# MIDIWidgetRevB.net
KiCad netlist of a schematic drawn in EAGLE
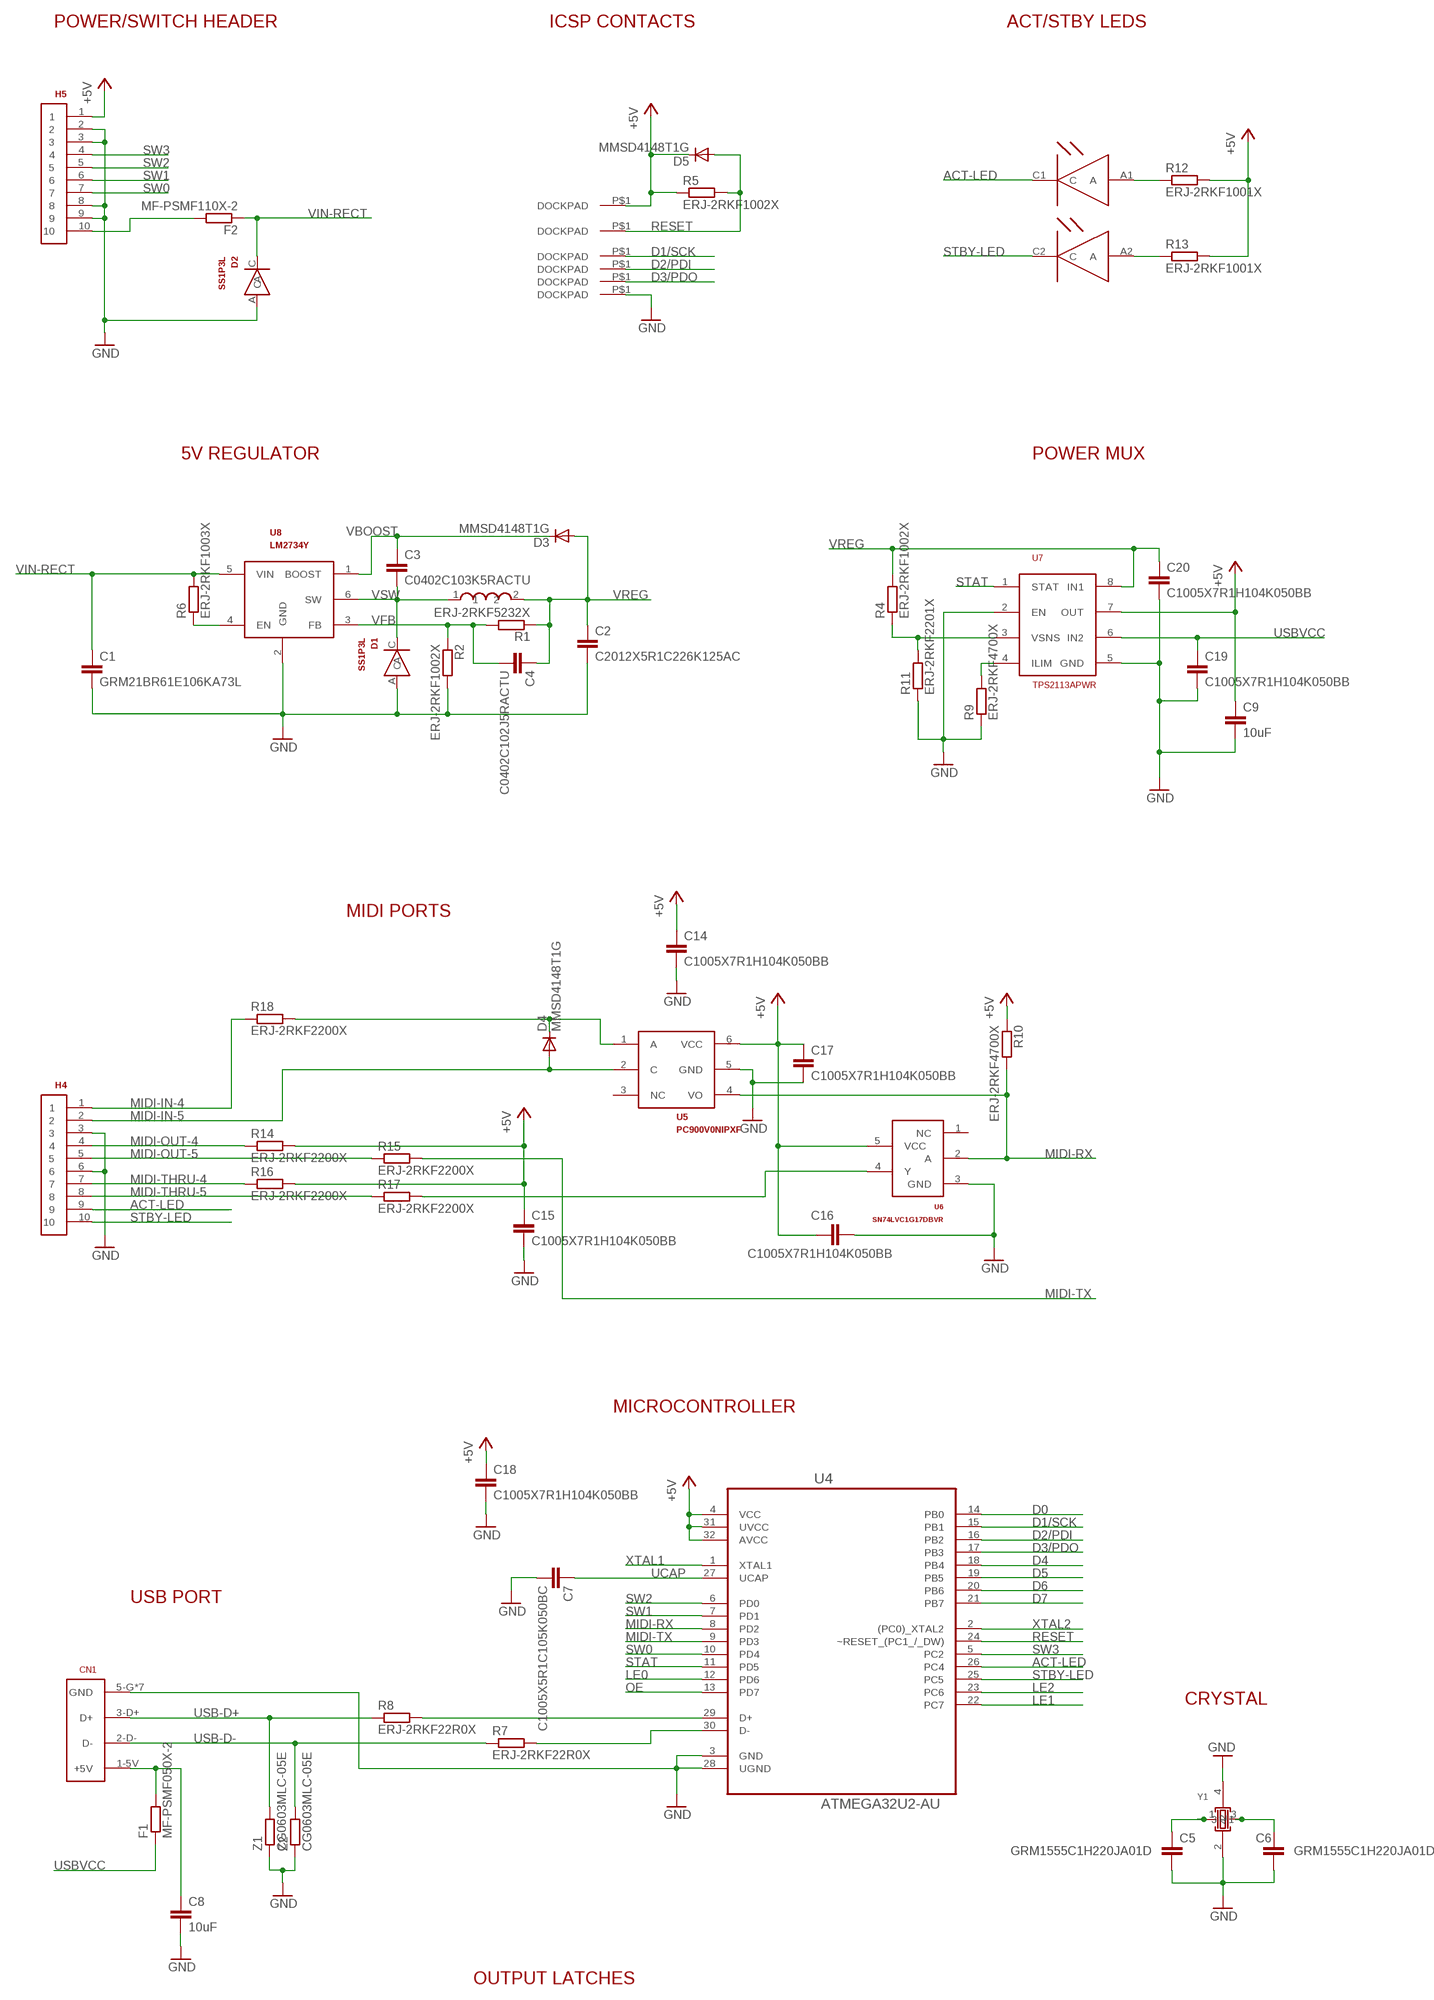
[diagram p0: schematic, sheet 1, part 1 of 2]
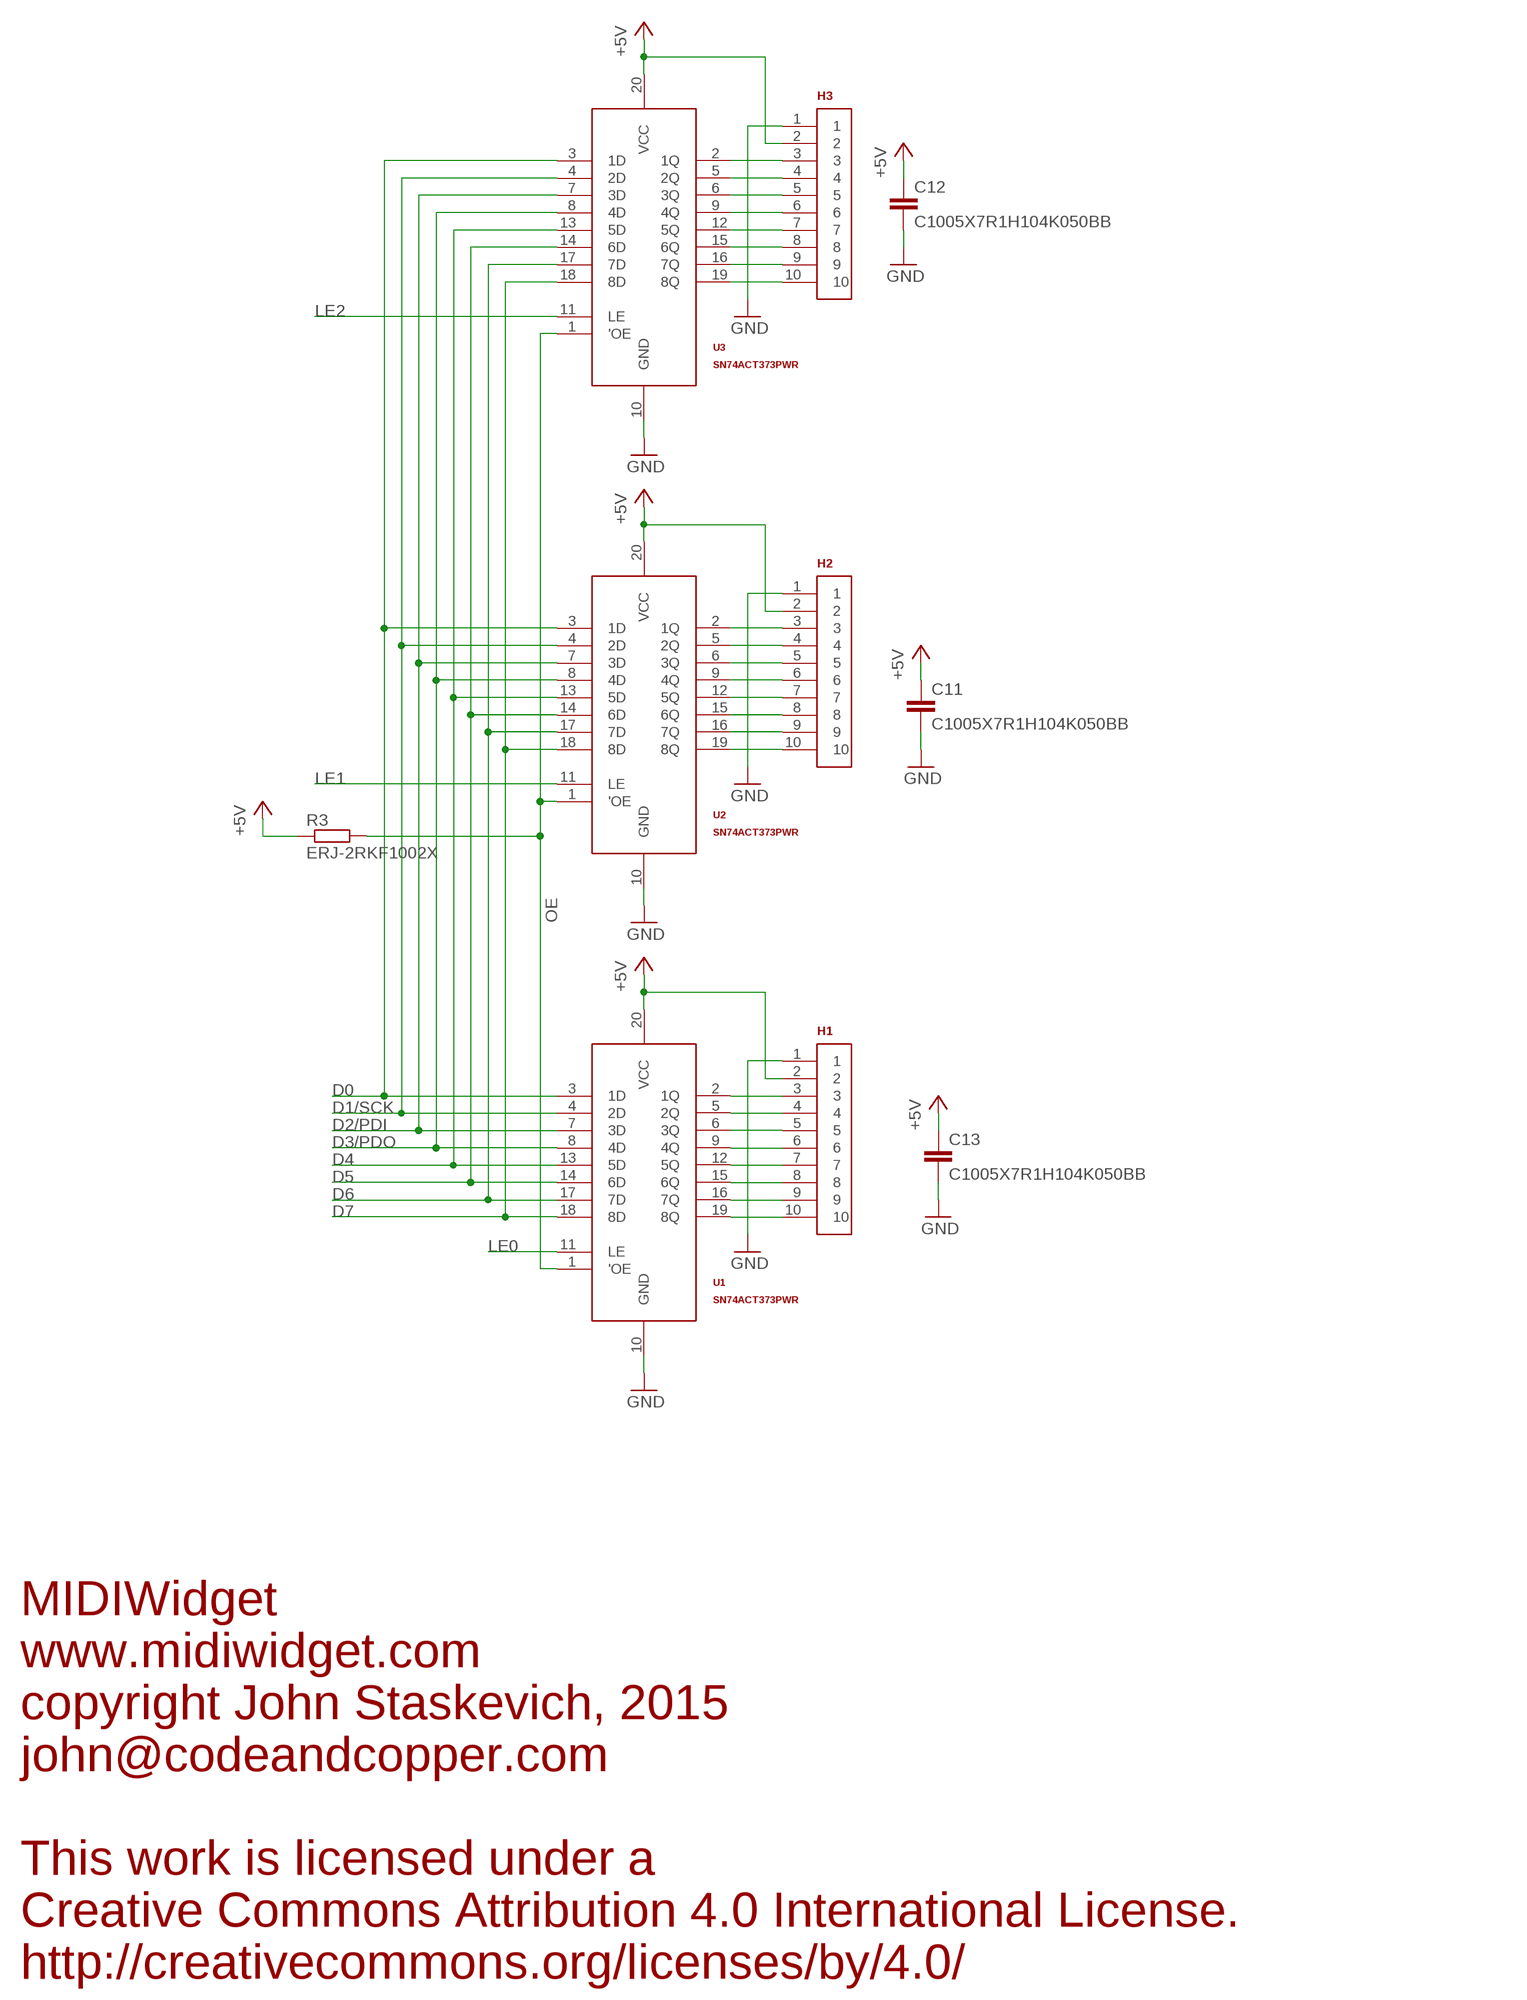
[diagram p1: schematic, sheet 1, part 2 of 2]

(export (version "E")
  (design (tool "Eeschema 10.0.6"))
  (components
    (comp (ref "C1")
      (value "GRM21BR61E106KA73L")
      (footprint "eagle-import:C0805")
      (libsource (lib "eagle-import") (part "C-EUC0805"))
    )
    (comp (ref "C2")
      (value "C2012X5R1C226K125AC")
      (footprint "eagle-import:C0805")
      (libsource (lib "eagle-import") (part "C-EUC0805"))
    )
    (comp (ref "C3")
      (value "C0402C103K5RACTU")
      (footprint "eagle-import:C0402")
      (libsource (lib "eagle-import") (part "C-EUC0402"))
    )
    (comp (ref "C4")
      (value "C0402C102J5RACTU")
      (footprint "eagle-import:C0402")
      (libsource (lib "eagle-import") (part "C-EUC0402"))
    )
    (comp (ref "C5")
      (value "GRM1555C1H220JA01D")
      (footprint "eagle-import:C0402")
      (libsource (lib "eagle-import") (part "C-EUC0402"))
    )
    (comp (ref "C6")
      (value "GRM1555C1H220JA01D")
      (footprint "eagle-import:C0402")
      (libsource (lib "eagle-import") (part "C-EUC0402"))
    )
    (comp (ref "C7")
      (value "C1005X5R1C105K050BC")
      (footprint "eagle-import:C0402")
      (libsource (lib "eagle-import") (part "C-EUC0402"))
    )
    (comp (ref "C8")
      (value "10uF")
      (footprint "eagle-import:C0805")
      (libsource (lib "eagle-import") (part "C-EUC0805"))
    )
    (comp (ref "C9")
      (value "10uF")
      (footprint "eagle-import:C0805")
      (libsource (lib "eagle-import") (part "C-EUC0805"))
    )
    (comp (ref "C11")
      (value "C1005X7R1H104K050BB")
      (footprint "eagle-import:C0402")
      (libsource (lib "eagle-import") (part "C-EUC0402"))
    )
    (comp (ref "C12")
      (value "C1005X7R1H104K050BB")
      (footprint "eagle-import:C0402")
      (libsource (lib "eagle-import") (part "C-EUC0402"))
    )
    (comp (ref "C13")
      (value "C1005X7R1H104K050BB")
      (footprint "eagle-import:C0402")
      (libsource (lib "eagle-import") (part "C-EUC0402"))
    )
    (comp (ref "C14")
      (value "C1005X7R1H104K050BB")
      (footprint "eagle-import:C0402")
      (libsource (lib "eagle-import") (part "C-EUC0402"))
    )
    (comp (ref "C15")
      (value "C1005X7R1H104K050BB")
      (footprint "eagle-import:C0402")
      (libsource (lib "eagle-import") (part "C-EUC0402"))
    )
    (comp (ref "C16")
      (value "C1005X7R1H104K050BB")
      (footprint "eagle-import:C0402")
      (libsource (lib "eagle-import") (part "C-EUC0402"))
    )
    (comp (ref "C17")
      (value "C1005X7R1H104K050BB")
      (footprint "eagle-import:C0402")
      (libsource (lib "eagle-import") (part "C-EUC0402"))
    )
    (comp (ref "C18")
      (value "C1005X7R1H104K050BB")
      (footprint "eagle-import:C0402")
      (libsource (lib "eagle-import") (part "C-EUC0402"))
    )
    (comp (ref "C19")
      (value "C1005X7R1H104K050BB")
      (footprint "eagle-import:C0402")
      (libsource (lib "eagle-import") (part "C-EUC0402"))
    )
    (comp (ref "C20")
      (value "C1005X7R1H104K050BB")
      (footprint "eagle-import:C0402")
      (libsource (lib "eagle-import") (part "C-EUC0402"))
    )
    (comp (ref "CN1")
      (value "10118192-0001LF")
      (footprint "eagle-import:USB-MICRO-B")
      (libsource (lib "eagle-import") (part "USB-B"))
    )
    (comp (ref "D1")
      (value "SS1P3L")
      (footprint "eagle-import:DO-220AA(SMP)")
      (libsource (lib "eagle-import") (part "DIODE"))
    )
    (comp (ref "D2")
      (value "SS1P3L")
      (footprint "eagle-import:DO-220AA(SMP)")
      (libsource (lib "eagle-import") (part "DIODE"))
    )
    (comp (ref "D3")
      (value "MMSD4148T1G")
      (footprint "eagle-import:SOD123")
      (libsource (lib "eagle-import") (part "1N4148SOD123"))
    )
    (comp (ref "D4")
      (value "MMSD4148T1G")
      (footprint "eagle-import:SOD123")
      (libsource (lib "eagle-import") (part "1N4148SOD123"))
    )
    (comp (ref "D5")
      (value "MMSD4148T1G")
      (footprint "eagle-import:SOD123")
      (libsource (lib "eagle-import") (part "1N4148SOD123"))
    )
    (comp (ref "DOCK-GND")
      (value "DOCKPAD")
      (footprint "eagle-import:DOCKPAD-ROUND-2.0MM")
      (libsource (lib "eagle-import") (part "DOCKPAD"))
    )
    (comp (ref "DOCK-PDI")
      (value "DOCKPAD")
      (footprint "eagle-import:DOCKPAD-ROUND-2.0MM")
      (libsource (lib "eagle-import") (part "DOCKPAD"))
    )
    (comp (ref "DOCK-PDO")
      (value "DOCKPAD")
      (footprint "eagle-import:DOCKPAD-ROUND-2.0MM")
      (libsource (lib "eagle-import") (part "DOCKPAD"))
    )
    (comp (ref "DOCK-RESET")
      (value "DOCKPAD")
      (footprint "eagle-import:DOCKPAD-ROUND-2.0MM")
      (libsource (lib "eagle-import") (part "DOCKPAD"))
    )
    (comp (ref "DOCK-SCK")
      (value "DOCKPAD")
      (footprint "eagle-import:DOCKPAD-ROUND-2.0MM")
      (libsource (lib "eagle-import") (part "DOCKPAD"))
    )
    (comp (ref "DOCK-VCC")
      (value "DOCKPAD")
      (footprint "eagle-import:DOCKPAD-ROUND-2.0MM")
      (libsource (lib "eagle-import") (part "DOCKPAD"))
    )
    (comp (ref "F1")
      (value "MF-PSMF050X-2")
      (footprint "eagle-import:R0805")
      (libsource (lib "eagle-import") (part "R-EU_R0805"))
    )
    (comp (ref "F2")
      (value "MF-PSMF110X-2")
      (footprint "eagle-import:R0805")
      (libsource (lib "eagle-import") (part "R-EU_R0805"))
    )
    (comp (ref "H1")
      (value "TERMINAL-BLOCK-10POS")
      (footprint "eagle-import:TB-2-54-10POS")
      (libsource (lib "eagle-import") (part "TERMINAL-BLOCK-10POS"))
    )
    (comp (ref "H2")
      (value "TERMINAL-BLOCK-10POS")
      (footprint "eagle-import:TB-2-54-10POS")
      (libsource (lib "eagle-import") (part "TERMINAL-BLOCK-10POS"))
    )
    (comp (ref "H3")
      (value "TERMINAL-BLOCK-10POS")
      (footprint "eagle-import:TB-2-54-10POS")
      (libsource (lib "eagle-import") (part "TERMINAL-BLOCK-10POS"))
    )
    (comp (ref "H4")
      (value "TERMINAL-BLOCK-10POS")
      (footprint "eagle-import:TB-2-54-10POS")
      (libsource (lib "eagle-import") (part "TERMINAL-BLOCK-10POS"))
    )
    (comp (ref "H5")
      (value "TERMINAL-BLOCK-10POS")
      (footprint "eagle-import:TB-2-54-10POS")
      (libsource (lib "eagle-import") (part "TERMINAL-BLOCK-10POS"))
    )
    (comp (ref "L1")
      (value "SLF7055T-220M1R7-3PF")
      (footprint "eagle-import:SLF7055")
      (libsource (lib "eagle-import") (part "INDUCTOR-SMT"))
    )
    (comp (ref "LED")
      (value "HSMF-C155")
      (footprint "eagle-import:LUMEX-1210-DUAL-LED")
      (libsource (lib "eagle-import") (part "DUAL-LED"))
    )
    (comp (ref "R1")
      (value "ERJ-2RKF5232X")
      (footprint "eagle-import:R0402")
      (libsource (lib "eagle-import") (part "R-EU_R0402"))
    )
    (comp (ref "R2")
      (value "ERJ-2RKF1002X")
      (footprint "eagle-import:R0402")
      (libsource (lib "eagle-import") (part "R-EU_R0402"))
    )
    (comp (ref "R3")
      (value "ERJ-2RKF1002X")
      (footprint "eagle-import:R0402")
      (libsource (lib "eagle-import") (part "R-EU_R0402"))
    )
    (comp (ref "R4")
      (value "ERJ-2RKF1002X")
      (footprint "eagle-import:R0402")
      (libsource (lib "eagle-import") (part "R-EU_R0402"))
    )
    (comp (ref "R5")
      (value "ERJ-2RKF1002X")
      (footprint "eagle-import:R0402")
      (libsource (lib "eagle-import") (part "R-EU_R0402"))
    )
    (comp (ref "R6")
      (value "ERJ-2RKF1003X")
      (footprint "eagle-import:R0402")
      (libsource (lib "eagle-import") (part "R-EU_R0402"))
    )
    (comp (ref "R7")
      (value "ERJ-2RKF22R0X")
      (footprint "eagle-import:R0402")
      (libsource (lib "eagle-import") (part "R-EU_R0402"))
    )
    (comp (ref "R8")
      (value "ERJ-2RKF22R0X")
      (footprint "eagle-import:R0402")
      (libsource (lib "eagle-import") (part "R-EU_R0402"))
    )
    (comp (ref "R9")
      (value "ERJ-2RKF4700X")
      (footprint "eagle-import:R0402")
      (libsource (lib "eagle-import") (part "R-EU_R0402"))
    )
    (comp (ref "R10")
      (value "ERJ-2RKF4700X")
      (footprint "eagle-import:R0402")
      (libsource (lib "eagle-import") (part "R-EU_R0402"))
    )
    (comp (ref "R11")
      (value "ERJ-2RKF2201X")
      (footprint "eagle-import:R0402")
      (libsource (lib "eagle-import") (part "R-EU_R0402"))
    )
    (comp (ref "R12")
      (value "ERJ-2RKF1001X")
      (footprint "eagle-import:R0402")
      (libsource (lib "eagle-import") (part "R-EU_R0402"))
    )
    (comp (ref "R13")
      (value "ERJ-2RKF1001X")
      (footprint "eagle-import:R0402")
      (libsource (lib "eagle-import") (part "R-EU_R0402"))
    )
    (comp (ref "R14")
      (value "ERJ-2RKF2200X")
      (footprint "eagle-import:R0402")
      (libsource (lib "eagle-import") (part "R-EU_R0402"))
    )
    (comp (ref "R15")
      (value "ERJ-2RKF2200X")
      (footprint "eagle-import:R0402")
      (libsource (lib "eagle-import") (part "R-EU_R0402"))
    )
    (comp (ref "R16")
      (value "ERJ-2RKF2200X")
      (footprint "eagle-import:R0402")
      (libsource (lib "eagle-import") (part "R-EU_R0402"))
    )
    (comp (ref "R17")
      (value "ERJ-2RKF2200X")
      (footprint "eagle-import:R0402")
      (libsource (lib "eagle-import") (part "R-EU_R0402"))
    )
    (comp (ref "R18")
      (value "ERJ-2RKF2200X")
      (footprint "eagle-import:R0402")
      (libsource (lib "eagle-import") (part "R-EU_R0402"))
    )
    (comp (ref "U1")
      (value "SN74ACT373PWR")
      (footprint "eagle-import:TSSOP-20")
      (libsource (lib "eagle-import") (part "74ABT373"))
    )
    (comp (ref "U2")
      (value "SN74ACT373PWR")
      (footprint "eagle-import:TSSOP-20")
      (libsource (lib "eagle-import") (part "74ABT373"))
    )
    (comp (ref "U3")
      (value "SN74ACT373PWR")
      (footprint "eagle-import:TSSOP-20")
      (libsource (lib "eagle-import") (part "74ABT373"))
    )
    (comp (ref "U4")
      (value "ATMEGA32U2-AU")
      (footprint "eagle-import:QFP80P900X900X120-32N")
      (libsource (lib "eagle-import") (part "ATMEGA32U2-AU"))
    )
    (comp (ref "U5")
      (value "PC900V0NIPXF")
      (footprint "eagle-import:SMT-6")
      (libsource (lib "eagle-import") (part "PC900V"))
    )
    (comp (ref "U6")
      (value "SN74LVC1G17DBVR")
      (footprint "eagle-import:SOT23-5-GOOD")
      (libsource (lib "eagle-import") (part "SN74LVC1G17"))
    )
    (comp (ref "U7")
      (value "TPS2113APWR")
      (footprint "eagle-import:TSSOP-8-NAKED")
      (libsource (lib "eagle-import") (part "TPS2112NAKED"))
    )
    (comp (ref "U8")
      (value "LM2734Y")
      (footprint "eagle-import:TSOT-6")
      (libsource (lib "eagle-import") (part "LM2734"))
    )
    (comp (ref "Y1")
      (value "403C35E16M00000")
      (footprint "eagle-import:CRYSTAL-32-25MM")
      (libsource (lib "eagle-import") (part "CTS-403-CRYSTAL"))
    )
    (comp (ref "Z1")
      (value "CG0603MLC-05E")
      (footprint "eagle-import:R0603")
      (libsource (lib "eagle-import") (part "R-EU_R0603"))
    )
    (comp (ref "Z2")
      (value "CG0603MLC-05E")
      (footprint "eagle-import:R0603")
      (libsource (lib "eagle-import") (part "R-EU_R0603"))
    )
  )
  (nets
    (net (code "1") (name "+5V") (class "Default")
      (node (ref "C11") (pin "1") (pinfunction "1_1") (pintype "passive"))
      (node (ref "C12") (pin "1") (pinfunction "1_1") (pintype "passive"))
      (node (ref "C13") (pin "1") (pinfunction "1_1") (pintype "passive"))
      (node (ref "C14") (pin "1") (pinfunction "1_1") (pintype "passive"))
      (node (ref "C15") (pin "1") (pinfunction "1_1") (pintype "passive"))
      (node (ref "C16") (pin "1") (pinfunction "1_1") (pintype "passive"))
      (node (ref "C17") (pin "1") (pinfunction "1_1") (pintype "passive"))
      (node (ref "C18") (pin "1") (pinfunction "1_1") (pintype "passive"))
      (node (ref "C9") (pin "1") (pinfunction "1_1") (pintype "passive"))
      (node (ref "D5") (pin "C") (pinfunction "C_C") (pintype "passive"))
      (node (ref "DOCK-VCC") (pin "P$1") (pinfunction "DOCKPAD_P$1") (pintype "bidirectional"))
      (node (ref "H1") (pin "2") (pinfunction "2_2") (pintype "bidirectional"))
      (node (ref "H2") (pin "2") (pinfunction "2_2") (pintype "bidirectional"))
      (node (ref "H3") (pin "2") (pinfunction "2_2") (pintype "bidirectional"))
      (node (ref "H5") (pin "1") (pinfunction "1_1") (pintype "bidirectional"))
      (node (ref "R10") (pin "1") (pinfunction "1_1") (pintype "passive"))
      (node (ref "R12") (pin "2") (pinfunction "2_2") (pintype "passive"))
      (node (ref "R13") (pin "2") (pinfunction "2_2") (pintype "passive"))
      (node (ref "R14") (pin "2") (pinfunction "2_2") (pintype "passive"))
      (node (ref "R16") (pin "2") (pinfunction "2_2") (pintype "passive"))
      (node (ref "R3") (pin "1") (pinfunction "1_1") (pintype "passive"))
      (node (ref "R5") (pin "1") (pinfunction "1_1") (pintype "passive"))
      (node (ref "U1") (pin "20") (pinfunction "VCC_20") (pintype "bidirectional"))
      (node (ref "U2") (pin "20") (pinfunction "VCC_20") (pintype "bidirectional"))
      (node (ref "U3") (pin "20") (pinfunction "VCC_20") (pintype "bidirectional"))
      (node (ref "U4") (pin "31") (pinfunction "UVCC_31") (pintype "power_in"))
      (node (ref "U4") (pin "32") (pinfunction "AVCC_32") (pintype "power_in"))
      (node (ref "U4") (pin "4") (pinfunction "VCC_4") (pintype "power_in"))
      (node (ref "U5") (pin "6") (pinfunction "VCC_6") (pintype "bidirectional"))
      (node (ref "U6") (pin "5") (pinfunction "VCC_5") (pintype "bidirectional"))
      (node (ref "U7") (pin "7") (pinfunction "OUT_7") (pintype "bidirectional"))
    )
    (net (code "2") (name "/ACT-LED") (class "Default")
      (node (ref "H4") (pin "9") (pinfunction "9_9") (pintype "bidirectional"))
      (node (ref "LED") (pin "C1") (pinfunction "C_C1") (pintype "bidirectional"))
      (node (ref "U4") (pin "26") (pinfunction "PC4_26") (pintype "bidirectional"))
    )
    (net (code "3") (name "/D0") (class "Default")
      (node (ref "U1") (pin "3") (pinfunction "1D_3") (pintype "bidirectional"))
      (node (ref "U2") (pin "3") (pinfunction "1D_3") (pintype "bidirectional"))
      (node (ref "U3") (pin "3") (pinfunction "1D_3") (pintype "bidirectional"))
      (node (ref "U4") (pin "14") (pinfunction "PB0_14") (pintype "bidirectional"))
    )
    (net (code "4") (name "/D1{slash}SCK") (class "Default")
      (node (ref "DOCK-SCK") (pin "P$1") (pinfunction "DOCKPAD_P$1") (pintype "bidirectional"))
      (node (ref "U1") (pin "4") (pinfunction "2D_4") (pintype "bidirectional"))
      (node (ref "U2") (pin "4") (pinfunction "2D_4") (pintype "bidirectional"))
      (node (ref "U3") (pin "4") (pinfunction "2D_4") (pintype "bidirectional"))
      (node (ref "U4") (pin "15") (pinfunction "PB1_15") (pintype "bidirectional"))
    )
    (net (code "5") (name "/D2{slash}PDI") (class "Default")
      (node (ref "DOCK-PDI") (pin "P$1") (pinfunction "DOCKPAD_P$1") (pintype "bidirectional"))
      (node (ref "U1") (pin "7") (pinfunction "3D_7") (pintype "bidirectional"))
      (node (ref "U2") (pin "7") (pinfunction "3D_7") (pintype "bidirectional"))
      (node (ref "U3") (pin "7") (pinfunction "3D_7") (pintype "bidirectional"))
      (node (ref "U4") (pin "16") (pinfunction "PB2_16") (pintype "bidirectional"))
    )
    (net (code "6") (name "/D3{slash}PDO") (class "Default")
      (node (ref "DOCK-PDO") (pin "P$1") (pinfunction "DOCKPAD_P$1") (pintype "bidirectional"))
      (node (ref "U1") (pin "8") (pinfunction "4D_8") (pintype "bidirectional"))
      (node (ref "U2") (pin "8") (pinfunction "4D_8") (pintype "bidirectional"))
      (node (ref "U3") (pin "8") (pinfunction "4D_8") (pintype "bidirectional"))
      (node (ref "U4") (pin "17") (pinfunction "PB3_17") (pintype "bidirectional"))
    )
    (net (code "7") (name "/D4") (class "Default")
      (node (ref "U1") (pin "13") (pinfunction "5D_13") (pintype "bidirectional"))
      (node (ref "U2") (pin "13") (pinfunction "5D_13") (pintype "bidirectional"))
      (node (ref "U3") (pin "13") (pinfunction "5D_13") (pintype "bidirectional"))
      (node (ref "U4") (pin "18") (pinfunction "PB4_18") (pintype "bidirectional"))
    )
    (net (code "8") (name "/D5") (class "Default")
      (node (ref "U1") (pin "14") (pinfunction "6D_14") (pintype "bidirectional"))
      (node (ref "U2") (pin "14") (pinfunction "6D_14") (pintype "bidirectional"))
      (node (ref "U3") (pin "14") (pinfunction "6D_14") (pintype "bidirectional"))
      (node (ref "U4") (pin "19") (pinfunction "PB5_19") (pintype "bidirectional"))
    )
    (net (code "9") (name "/D6") (class "Default")
      (node (ref "U1") (pin "17") (pinfunction "7D_17") (pintype "bidirectional"))
      (node (ref "U2") (pin "17") (pinfunction "7D_17") (pintype "bidirectional"))
      (node (ref "U3") (pin "17") (pinfunction "7D_17") (pintype "bidirectional"))
      (node (ref "U4") (pin "20") (pinfunction "PB6_20") (pintype "bidirectional"))
    )
    (net (code "10") (name "/D7") (class "Default")
      (node (ref "U1") (pin "18") (pinfunction "8D_18") (pintype "bidirectional"))
      (node (ref "U2") (pin "18") (pinfunction "8D_18") (pintype "bidirectional"))
      (node (ref "U3") (pin "18") (pinfunction "8D_18") (pintype "bidirectional"))
      (node (ref "U4") (pin "21") (pinfunction "PB7_21") (pintype "bidirectional"))
    )
    (net (code "11") (name "/LE0") (class "Default")
      (node (ref "U1") (pin "11") (pinfunction "LE_11") (pintype "bidirectional"))
      (node (ref "U4") (pin "12") (pinfunction "PD6_12") (pintype "bidirectional"))
    )
    (net (code "12") (name "/LE1") (class "Default")
      (node (ref "U2") (pin "11") (pinfunction "LE_11") (pintype "bidirectional"))
      (node (ref "U4") (pin "22") (pinfunction "PC7_22") (pintype "bidirectional"))
    )
    (net (code "13") (name "/LE2") (class "Default")
      (node (ref "U3") (pin "11") (pinfunction "LE_11") (pintype "bidirectional"))
      (node (ref "U4") (pin "23") (pinfunction "PC6_23") (pintype "bidirectional"))
    )
    (net (code "14") (name "/MIDI-IN-4") (class "Default")
      (node (ref "H4") (pin "1") (pinfunction "1_1") (pintype "bidirectional"))
      (node (ref "R18") (pin "1") (pinfunction "1_1") (pintype "passive"))
    )
    (net (code "15") (name "/MIDI-IN-5") (class "Default")
      (node (ref "D4") (pin "A") (pinfunction "A_A") (pintype "passive"))
      (node (ref "H4") (pin "2") (pinfunction "2_2") (pintype "bidirectional"))
      (node (ref "U5") (pin "2") (pinfunction "C_2") (pintype "bidirectional"))
    )
    (net (code "16") (name "/MIDI-OUT-4") (class "Default")
      (node (ref "H4") (pin "4") (pinfunction "4_4") (pintype "bidirectional"))
      (node (ref "R14") (pin "1") (pinfunction "1_1") (pintype "passive"))
    )
    (net (code "17") (name "/MIDI-OUT-5") (class "Default")
      (node (ref "H4") (pin "5") (pinfunction "5_5") (pintype "bidirectional"))
      (node (ref "R15") (pin "1") (pinfunction "1_1") (pintype "passive"))
    )
    (net (code "18") (name "/MIDI-RX") (class "Default")
      (node (ref "R10") (pin "2") (pinfunction "2_2") (pintype "passive"))
      (node (ref "U4") (pin "8") (pinfunction "PD2_8") (pintype "bidirectional"))
      (node (ref "U5") (pin "4") (pinfunction "VO_4") (pintype "bidirectional"))
      (node (ref "U6") (pin "2") (pinfunction "A_2") (pintype "bidirectional"))
    )
    (net (code "19") (name "/MIDI-THRU-4") (class "Default")
      (node (ref "H4") (pin "7") (pinfunction "7_7") (pintype "bidirectional"))
      (node (ref "R16") (pin "1") (pinfunction "1_1") (pintype "passive"))
    )
    (net (code "20") (name "/MIDI-THRU-5") (class "Default")
      (node (ref "H4") (pin "8") (pinfunction "8_8") (pintype "bidirectional"))
      (node (ref "R17") (pin "1") (pinfunction "1_1") (pintype "passive"))
    )
    (net (code "21") (name "/MIDI-TX") (class "Default")
      (node (ref "R15") (pin "2") (pinfunction "2_2") (pintype "passive"))
      (node (ref "U4") (pin "9") (pinfunction "PD3_9") (pintype "bidirectional"))
    )
    (net (code "22") (name "/OE") (class "Default")
      (node (ref "R3") (pin "2") (pinfunction "2_2") (pintype "passive"))
      (node (ref "U1") (pin "1") (pinfunction "'OE_1") (pintype "bidirectional"))
      (node (ref "U2") (pin "1") (pinfunction "'OE_1") (pintype "bidirectional"))
      (node (ref "U3") (pin "1") (pinfunction "'OE_1") (pintype "bidirectional"))
      (node (ref "U4") (pin "13") (pinfunction "PD7_13") (pintype "bidirectional"))
    )
    (net (code "23") (name "/RESET") (class "Default")
      (node (ref "D5") (pin "A") (pinfunction "A_A") (pintype "passive"))
      (node (ref "DOCK-RESET") (pin "P$1") (pinfunction "DOCKPAD_P$1") (pintype "bidirectional"))
      (node (ref "R5") (pin "2") (pinfunction "2_2") (pintype "passive"))
      (node (ref "U4") (pin "24") (pinfunction "~{RESET_(PC1_/_DW})_24") (pintype "bidirectional"))
    )
    (net (code "24") (name "/STAT") (class "Default")
      (node (ref "U4") (pin "11") (pinfunction "PD5_11") (pintype "bidirectional"))
      (node (ref "U7") (pin "1") (pinfunction "STAT_1") (pintype "bidirectional"))
    )
    (net (code "25") (name "/STBY-LED") (class "Default")
      (node (ref "H4") (pin "10") (pinfunction "10_10") (pintype "bidirectional"))
      (node (ref "LED") (pin "C2") (pinfunction "C_C2") (pintype "bidirectional"))
      (node (ref "U4") (pin "25") (pinfunction "PC5_25") (pintype "bidirectional"))
    )
    (net (code "26") (name "/SW0") (class "Default")
      (node (ref "H5") (pin "7") (pinfunction "7_7") (pintype "bidirectional"))
      (node (ref "U4") (pin "10") (pinfunction "PD4_10") (pintype "bidirectional"))
    )
    (net (code "27") (name "/SW1") (class "Default")
      (node (ref "H5") (pin "6") (pinfunction "6_6") (pintype "bidirectional"))
      (node (ref "U4") (pin "7") (pinfunction "PD1_7") (pintype "bidirectional"))
    )
    (net (code "28") (name "/SW2") (class "Default")
      (node (ref "H5") (pin "5") (pinfunction "5_5") (pintype "bidirectional"))
      (node (ref "U4") (pin "6") (pinfunction "PD0_6") (pintype "bidirectional"))
    )
    (net (code "29") (name "/SW3") (class "Default")
      (node (ref "H5") (pin "4") (pinfunction "4_4") (pintype "bidirectional"))
      (node (ref "U4") (pin "5") (pinfunction "PC2_5") (pintype "bidirectional"))
    )
    (net (code "30") (name "/UCAP") (class "Default")
      (node (ref "C7") (pin "1") (pinfunction "1_1") (pintype "passive"))
      (node (ref "U4") (pin "27") (pinfunction "UCAP_27") (pintype "power_in"))
    )
    (net (code "31") (name "/USB-D+") (class "Default")
      (node (ref "CN1") (pin "3-D+") (pinfunction "D+_3-D+") (pintype "bidirectional"))
      (node (ref "R8") (pin "1") (pinfunction "1_1") (pintype "passive"))
      (node (ref "Z1") (pin "2") (pinfunction "2_2") (pintype "passive"))
    )
    (net (code "32") (name "/USB-D-") (class "Default")
      (node (ref "CN1") (pin "2-D-") (pinfunction "D-_2-D-") (pintype "bidirectional"))
      (node (ref "R7") (pin "1") (pinfunction "1_1") (pintype "passive"))
      (node (ref "Z2") (pin "2") (pinfunction "2_2") (pintype "passive"))
    )
    (net (code "33") (name "/USBVCC") (class "Default")
      (node (ref "C19") (pin "1") (pinfunction "1_1") (pintype "passive"))
      (node (ref "F1") (pin "1") (pinfunction "1_1") (pintype "passive"))
      (node (ref "U7") (pin "6") (pinfunction "IN2_6") (pintype "bidirectional"))
    )
    (net (code "34") (name "/VBOOST") (class "Default")
      (node (ref "C3") (pin "1") (pinfunction "1_1") (pintype "passive"))
      (node (ref "D3") (pin "C") (pinfunction "C_C") (pintype "passive"))
      (node (ref "U8") (pin "1") (pinfunction "BOOST_1") (pintype "bidirectional"))
    )
    (net (code "35") (name "/VFB") (class "Default")
      (node (ref "C4") (pin "2") (pinfunction "2_2") (pintype "passive"))
      (node (ref "R1") (pin "2") (pinfunction "2_2") (pintype "passive"))
      (node (ref "R2") (pin "1") (pinfunction "1_1") (pintype "passive"))
      (node (ref "U8") (pin "3") (pinfunction "FB_3") (pintype "bidirectional"))
    )
    (net (code "36") (name "/VIN-RECT") (class "Default")
      (node (ref "C1") (pin "1") (pinfunction "1_1") (pintype "passive"))
      (node (ref "D2") (pin "C") (pinfunction "C_C") (pintype "bidirectional"))
      (node (ref "F2") (pin "1") (pinfunction "1_1") (pintype "passive"))
      (node (ref "R6") (pin "2") (pinfunction "2_2") (pintype "passive"))
      (node (ref "U8") (pin "5") (pinfunction "VIN_5") (pintype "bidirectional"))
    )
    (net (code "37") (name "/VREG") (class "Default")
      (node (ref "C2") (pin "1") (pinfunction "1_1") (pintype "passive"))
      (node (ref "C20") (pin "1") (pinfunction "1_1") (pintype "passive"))
      (node (ref "C4") (pin "1") (pinfunction "1_1") (pintype "passive"))
      (node (ref "D3") (pin "A") (pinfunction "A_A") (pintype "passive"))
      (node (ref "L1") (pin "2") (pinfunction "2_2") (pintype "bidirectional"))
      (node (ref "R1") (pin "1") (pinfunction "1_1") (pintype "passive"))
      (node (ref "R4") (pin "2") (pinfunction "2_2") (pintype "passive"))
      (node (ref "U7") (pin "8") (pinfunction "IN1_8") (pintype "bidirectional"))
    )
    (net (code "38") (name "/VSW") (class "Default")
      (node (ref "C3") (pin "2") (pinfunction "2_2") (pintype "passive"))
      (node (ref "D1") (pin "C") (pinfunction "C_C") (pintype "bidirectional"))
      (node (ref "L1") (pin "1") (pinfunction "1_1") (pintype "bidirectional"))
      (node (ref "U8") (pin "6") (pinfunction "SW_6") (pintype "bidirectional"))
    )
    (net (code "39") (name "/XTAL1") (class "Default")
      (node (ref "C5") (pin "1") (pinfunction "1_1") (pintype "passive"))
      (node (ref "U4") (pin "1") (pinfunction "XTAL1_1") (pintype "input"))
      (node (ref "Y1") (pin "1") (pinfunction "1_1") (pintype "bidirectional"))
    )
    (net (code "40") (name "/XTAL2") (class "Default")
      (node (ref "C6") (pin "1") (pinfunction "1_1") (pintype "passive"))
      (node (ref "U4") (pin "2") (pinfunction "(PC0)_XTAL2_2") (pintype "bidirectional"))
      (node (ref "Y1") (pin "3") (pinfunction "3_3") (pintype "bidirectional"))
    )
    (net (code "41") (name "GND") (class "Default")
      (node (ref "C1") (pin "2") (pinfunction "2_2") (pintype "passive"))
      (node (ref "C11") (pin "2") (pinfunction "2_2") (pintype "passive"))
      (node (ref "C12") (pin "2") (pinfunction "2_2") (pintype "passive"))
      (node (ref "C13") (pin "2") (pinfunction "2_2") (pintype "passive"))
      (node (ref "C14") (pin "2") (pinfunction "2_2") (pintype "passive"))
      (node (ref "C15") (pin "2") (pinfunction "2_2") (pintype "passive"))
      (node (ref "C16") (pin "2") (pinfunction "2_2") (pintype "passive"))
      (node (ref "C17") (pin "2") (pinfunction "2_2") (pintype "passive"))
      (node (ref "C18") (pin "2") (pinfunction "2_2") (pintype "passive"))
      (node (ref "C19") (pin "2") (pinfunction "2_2") (pintype "passive"))
      (node (ref "C2") (pin "2") (pinfunction "2_2") (pintype "passive"))
      (node (ref "C20") (pin "2") (pinfunction "2_2") (pintype "passive"))
      (node (ref "C5") (pin "2") (pinfunction "2_2") (pintype "passive"))
      (node (ref "C6") (pin "2") (pinfunction "2_2") (pintype "passive"))
      (node (ref "C7") (pin "2") (pinfunction "2_2") (pintype "passive"))
      (node (ref "C8") (pin "2") (pinfunction "2_2") (pintype "passive"))
      (node (ref "C9") (pin "2") (pinfunction "2_2") (pintype "passive"))
      (node (ref "CN1") (pin "5-G") (pinfunction "GND_5-G") (pintype "bidirectional"))
      (node (ref "CN1") (pin "P$1") (pinfunction "GND_P$1") (pintype "bidirectional"))
      (node (ref "CN1") (pin "P$10") (pinfunction "GND_P$10") (pintype "bidirectional"))
      (node (ref "CN1") (pin "P$11") (pinfunction "GND_P$11") (pintype "bidirectional"))
      (node (ref "CN1") (pin "P$2") (pinfunction "GND_P$2") (pintype "bidirectional"))
      (node (ref "CN1") (pin "P$3") (pinfunction "GND_P$3") (pintype "bidirectional"))
      (node (ref "CN1") (pin "P$4") (pinfunction "GND_P$4") (pintype "bidirectional"))
      (node (ref "D1") (pin "A") (pinfunction "A_A") (pintype "bidirectional"))
      (node (ref "D2") (pin "A") (pinfunction "A_A") (pintype "bidirectional"))
      (node (ref "DOCK-GND") (pin "P$1") (pinfunction "DOCKPAD_P$1") (pintype "bidirectional"))
      (node (ref "H1") (pin "1") (pinfunction "1_1") (pintype "bidirectional"))
      (node (ref "H2") (pin "1") (pinfunction "1_1") (pintype "bidirectional"))
      (node (ref "H3") (pin "1") (pinfunction "1_1") (pintype "bidirectional"))
      (node (ref "H4") (pin "3") (pinfunction "3_3") (pintype "bidirectional"))
      (node (ref "H4") (pin "6") (pinfunction "6_6") (pintype "bidirectional"))
      (node (ref "H5") (pin "2") (pinfunction "2_2") (pintype "bidirectional"))
      (node (ref "H5") (pin "3") (pinfunction "3_3") (pintype "bidirectional"))
      (node (ref "H5") (pin "8") (pinfunction "8_8") (pintype "bidirectional"))
      (node (ref "H5") (pin "9") (pinfunction "9_9") (pintype "bidirectional"))
      (node (ref "R11") (pin "1") (pinfunction "1_1") (pintype "passive"))
      (node (ref "R2") (pin "2") (pinfunction "2_2") (pintype "passive"))
      (node (ref "R9") (pin "1") (pinfunction "1_1") (pintype "passive"))
      (node (ref "U1") (pin "10") (pinfunction "GND_10") (pintype "bidirectional"))
      (node (ref "U2") (pin "10") (pinfunction "GND_10") (pintype "bidirectional"))
      (node (ref "U3") (pin "10") (pinfunction "GND_10") (pintype "bidirectional"))
      (node (ref "U4") (pin "28") (pinfunction "UGND_28") (pintype "passive"))
      (node (ref "U4") (pin "3") (pinfunction "GND_3") (pintype "passive"))
      (node (ref "U5") (pin "5") (pinfunction "GND_5") (pintype "bidirectional"))
      (node (ref "U6") (pin "3") (pinfunction "GND_3") (pintype "bidirectional"))
      (node (ref "U7") (pin "2") (pinfunction "EN_2") (pintype "bidirectional"))
      (node (ref "U7") (pin "5") (pinfunction "GND_5") (pintype "bidirectional"))
      (node (ref "U8") (pin "2") (pinfunction "GND_2") (pintype "bidirectional"))
      (node (ref "Y1") (pin "2") (pinfunction "2_2") (pintype "bidirectional"))
      (node (ref "Y1") (pin "4") (pinfunction "4_4") (pintype "bidirectional"))
      (node (ref "Z1") (pin "1") (pinfunction "1_1") (pintype "passive"))
      (node (ref "Z2") (pin "1") (pinfunction "1_1") (pintype "passive"))
    )
    (net (code "42") (name "Net-(CN1-+5V)") (class "Default")
      (node (ref "C8") (pin "1") (pinfunction "1_1") (pintype "passive"))
      (node (ref "CN1") (pin "1-5V") (pinfunction "+5V_1-5V") (pintype "bidirectional"))
      (node (ref "F1") (pin "2") (pinfunction "2_2") (pintype "passive"))
    )
    (net (code "43") (name "Net-(F2-Pad2)") (class "Default")
      (node (ref "F2") (pin "2") (pinfunction "2_2") (pintype "passive"))
      (node (ref "H5") (pin "10") (pinfunction "10_10") (pintype "bidirectional"))
    )
    (net (code "44") (name "Net-(LEDA-A)") (class "Default")
      (node (ref "LED") (pin "A1") (pinfunction "A_A1") (pintype "bidirectional"))
      (node (ref "R12") (pin "1") (pinfunction "1_1") (pintype "passive"))
    )
    (net (code "45") (name "Net-(LEDB-A)") (class "Default")
      (node (ref "LED") (pin "A2") (pinfunction "A_A2") (pintype "bidirectional"))
      (node (ref "R13") (pin "1") (pinfunction "1_1") (pintype "passive"))
    )
    (net (code "46") (name "Net-(U1-1Q)") (class "Default")
      (node (ref "H1") (pin "3") (pinfunction "3_3") (pintype "bidirectional"))
      (node (ref "U1") (pin "2") (pinfunction "1Q_2") (pintype "bidirectional"))
    )
    (net (code "47") (name "Net-(U1-2Q)") (class "Default")
      (node (ref "H1") (pin "4") (pinfunction "4_4") (pintype "bidirectional"))
      (node (ref "U1") (pin "5") (pinfunction "2Q_5") (pintype "bidirectional"))
    )
    (net (code "48") (name "Net-(U1-3Q)") (class "Default")
      (node (ref "H1") (pin "5") (pinfunction "5_5") (pintype "bidirectional"))
      (node (ref "U1") (pin "6") (pinfunction "3Q_6") (pintype "bidirectional"))
    )
    (net (code "49") (name "Net-(U1-4Q)") (class "Default")
      (node (ref "H1") (pin "6") (pinfunction "6_6") (pintype "bidirectional"))
      (node (ref "U1") (pin "9") (pinfunction "4Q_9") (pintype "bidirectional"))
    )
    (net (code "50") (name "Net-(U1-5Q)") (class "Default")
      (node (ref "H1") (pin "7") (pinfunction "7_7") (pintype "bidirectional"))
      (node (ref "U1") (pin "12") (pinfunction "5Q_12") (pintype "bidirectional"))
    )
    (net (code "51") (name "Net-(U1-6Q)") (class "Default")
      (node (ref "H1") (pin "8") (pinfunction "8_8") (pintype "bidirectional"))
      (node (ref "U1") (pin "15") (pinfunction "6Q_15") (pintype "bidirectional"))
    )
    (net (code "52") (name "Net-(U1-7Q)") (class "Default")
      (node (ref "H1") (pin "9") (pinfunction "9_9") (pintype "bidirectional"))
      (node (ref "U1") (pin "16") (pinfunction "7Q_16") (pintype "bidirectional"))
    )
    (net (code "53") (name "Net-(U1-8Q)") (class "Default")
      (node (ref "H1") (pin "10") (pinfunction "10_10") (pintype "bidirectional"))
      (node (ref "U1") (pin "19") (pinfunction "8Q_19") (pintype "bidirectional"))
    )
    (net (code "54") (name "Net-(U2-1Q)") (class "Default")
      (node (ref "H2") (pin "3") (pinfunction "3_3") (pintype "bidirectional"))
      (node (ref "U2") (pin "2") (pinfunction "1Q_2") (pintype "bidirectional"))
    )
    (net (code "55") (name "Net-(U2-2Q)") (class "Default")
      (node (ref "H2") (pin "4") (pinfunction "4_4") (pintype "bidirectional"))
      (node (ref "U2") (pin "5") (pinfunction "2Q_5") (pintype "bidirectional"))
    )
    (net (code "56") (name "Net-(U2-3Q)") (class "Default")
      (node (ref "H2") (pin "5") (pinfunction "5_5") (pintype "bidirectional"))
      (node (ref "U2") (pin "6") (pinfunction "3Q_6") (pintype "bidirectional"))
    )
    (net (code "57") (name "Net-(U2-4Q)") (class "Default")
      (node (ref "H2") (pin "6") (pinfunction "6_6") (pintype "bidirectional"))
      (node (ref "U2") (pin "9") (pinfunction "4Q_9") (pintype "bidirectional"))
    )
    (net (code "58") (name "Net-(U2-5Q)") (class "Default")
      (node (ref "H2") (pin "7") (pinfunction "7_7") (pintype "bidirectional"))
      (node (ref "U2") (pin "12") (pinfunction "5Q_12") (pintype "bidirectional"))
    )
    (net (code "59") (name "Net-(U2-6Q)") (class "Default")
      (node (ref "H2") (pin "8") (pinfunction "8_8") (pintype "bidirectional"))
      (node (ref "U2") (pin "15") (pinfunction "6Q_15") (pintype "bidirectional"))
    )
    (net (code "60") (name "Net-(U2-7Q)") (class "Default")
      (node (ref "H2") (pin "9") (pinfunction "9_9") (pintype "bidirectional"))
      (node (ref "U2") (pin "16") (pinfunction "7Q_16") (pintype "bidirectional"))
    )
    (net (code "61") (name "Net-(U2-8Q)") (class "Default")
      (node (ref "H2") (pin "10") (pinfunction "10_10") (pintype "bidirectional"))
      (node (ref "U2") (pin "19") (pinfunction "8Q_19") (pintype "bidirectional"))
    )
    (net (code "62") (name "Net-(U3-1Q)") (class "Default")
      (node (ref "H3") (pin "3") (pinfunction "3_3") (pintype "bidirectional"))
      (node (ref "U3") (pin "2") (pinfunction "1Q_2") (pintype "bidirectional"))
    )
    (net (code "63") (name "Net-(U3-2Q)") (class "Default")
      (node (ref "H3") (pin "4") (pinfunction "4_4") (pintype "bidirectional"))
      (node (ref "U3") (pin "5") (pinfunction "2Q_5") (pintype "bidirectional"))
    )
    (net (code "64") (name "Net-(U3-3Q)") (class "Default")
      (node (ref "H3") (pin "5") (pinfunction "5_5") (pintype "bidirectional"))
      (node (ref "U3") (pin "6") (pinfunction "3Q_6") (pintype "bidirectional"))
    )
    (net (code "65") (name "Net-(U3-4Q)") (class "Default")
      (node (ref "H3") (pin "6") (pinfunction "6_6") (pintype "bidirectional"))
      (node (ref "U3") (pin "9") (pinfunction "4Q_9") (pintype "bidirectional"))
    )
    (net (code "66") (name "Net-(U3-5Q)") (class "Default")
      (node (ref "H3") (pin "7") (pinfunction "7_7") (pintype "bidirectional"))
      (node (ref "U3") (pin "12") (pinfunction "5Q_12") (pintype "bidirectional"))
    )
    (net (code "67") (name "Net-(U3-6Q)") (class "Default")
      (node (ref "H3") (pin "8") (pinfunction "8_8") (pintype "bidirectional"))
      (node (ref "U3") (pin "15") (pinfunction "6Q_15") (pintype "bidirectional"))
    )
    (net (code "68") (name "Net-(U3-7Q)") (class "Default")
      (node (ref "H3") (pin "9") (pinfunction "9_9") (pintype "bidirectional"))
      (node (ref "U3") (pin "16") (pinfunction "7Q_16") (pintype "bidirectional"))
    )
    (net (code "69") (name "Net-(U3-8Q)") (class "Default")
      (node (ref "H3") (pin "10") (pinfunction "10_10") (pintype "bidirectional"))
      (node (ref "U3") (pin "19") (pinfunction "8Q_19") (pintype "bidirectional"))
    )
    (net (code "70") (name "Net-(U4-D+)") (class "Default")
      (node (ref "R8") (pin "2") (pinfunction "2_2") (pintype "passive"))
      (node (ref "U4") (pin "29") (pinfunction "D+_29") (pintype "bidirectional"))
    )
    (net (code "71") (name "Net-(U4-D-)") (class "Default")
      (node (ref "R7") (pin "2") (pinfunction "2_2") (pintype "passive"))
      (node (ref "U4") (pin "30") (pinfunction "D-_30") (pintype "bidirectional"))
    )
    (net (code "72") (name "Net-(U5-A)") (class "Default")
      (node (ref "D4") (pin "C") (pinfunction "C_C") (pintype "passive"))
      (node (ref "R18") (pin "2") (pinfunction "2_2") (pintype "passive"))
      (node (ref "U5") (pin "1") (pinfunction "A_1") (pintype "bidirectional"))
    )
    (net (code "73") (name "Net-(U6-Y)") (class "Default")
      (node (ref "R17") (pin "2") (pinfunction "2_2") (pintype "passive"))
      (node (ref "U6") (pin "4") (pinfunction "Y_4") (pintype "bidirectional"))
    )
    (net (code "74") (name "Net-(U7-ILIM)") (class "Default")
      (node (ref "R9") (pin "2") (pinfunction "2_2") (pintype "passive"))
      (node (ref "U7") (pin "4") (pinfunction "ILIM_4") (pintype "bidirectional"))
    )
    (net (code "75") (name "Net-(U7-VSNS)") (class "Default")
      (node (ref "R11") (pin "2") (pinfunction "2_2") (pintype "passive"))
      (node (ref "R4") (pin "1") (pinfunction "1_1") (pintype "passive"))
      (node (ref "U7") (pin "3") (pinfunction "VSNS_3") (pintype "bidirectional"))
    )
    (net (code "76") (name "Net-(U8-EN)") (class "Default")
      (node (ref "R6") (pin "1") (pinfunction "1_1") (pintype "passive"))
      (node (ref "U8") (pin "4") (pinfunction "EN_4") (pintype "bidirectional"))
    )
    (net (code "77") (name "unconnected-(U5-NC-Pad3)") (class "Default")
      (node (ref "U5") (pin "3") (pinfunction "NC_3") (pintype "bidirectional"))
    )
    (net (code "78") (name "unconnected-(U6-NC-Pad1)") (class "Default")
      (node (ref "U6") (pin "1") (pinfunction "NC_1") (pintype "bidirectional"))
    )
  )
)
